# Medusa-AI-ESP.net
KiCad netlist of a schematic drawn in Altium Designer
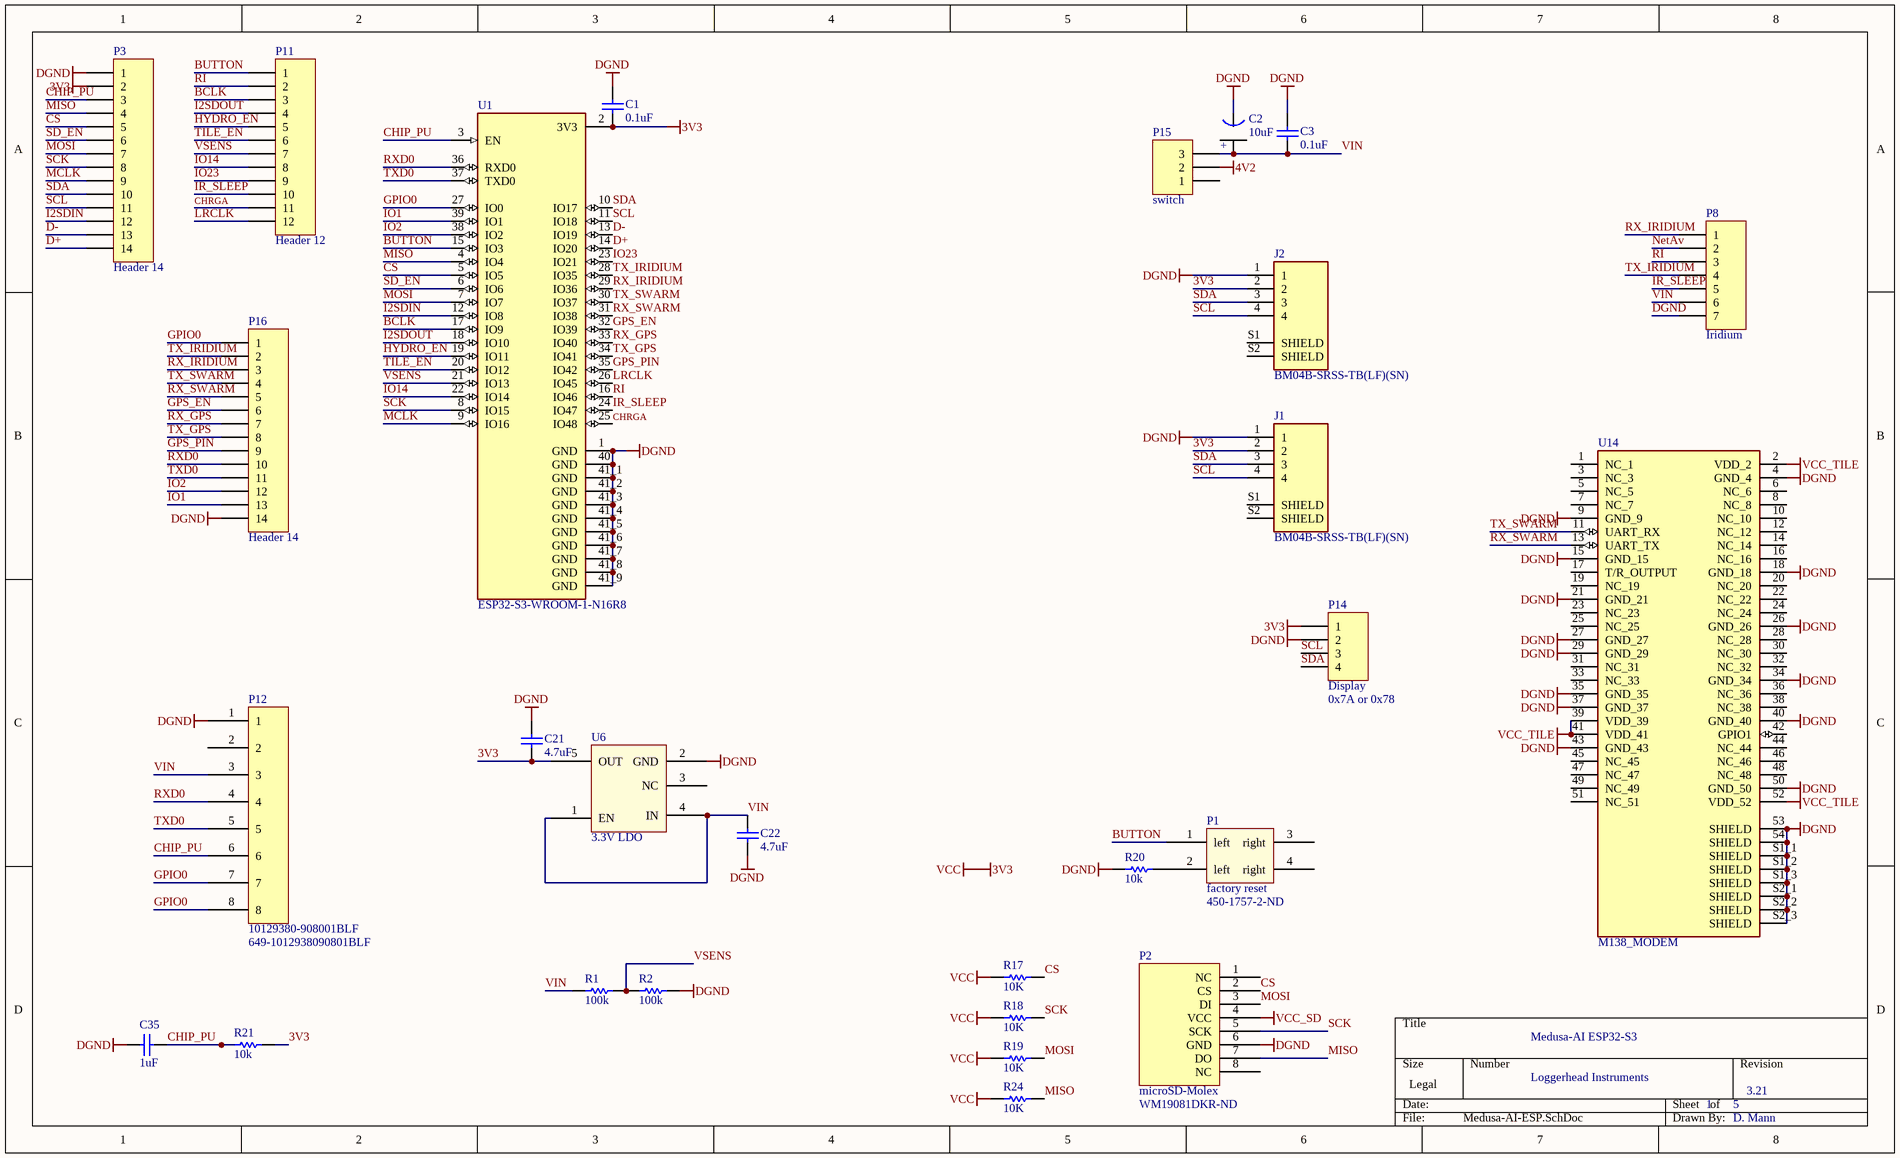
[diagram p0: Medusa-AI-ESP.SchDoc]

(export (version "E")
  (design (tool "Eeschema 10.0.6"))
  (components
    (comp (ref "C1")
      (value "0.1uF")
      (footprint "0402")
      (description "Ceramic Chip Capacitor - Standard")
      (fields (field (name "PUBLISHER") "Altium Limited"))
      (libsource (lib "KEMET Chip Capacitor") (part "C0402"))
    )
    (comp (ref "C2") (value "10uF") (footprint "Tant0805") (libsource (lib "Loggerhead") (part "Tant0805")))
    (comp (ref "C3")
      (value "0.1uF")
      (footprint "0402")
      (description "Ceramic Chip Capacitor - Standard")
      (fields (field (name "PUBLISHER") "Altium Limited"))
      (libsource (lib "KEMET Chip Capacitor") (part "C0402"))
    )
    (comp (ref "C21")
      (value "4.7uF")
      (footprint "0402")
      (description "Ceramic Chip Capacitor - Standard")
      (fields (field (name "PUBLISHER") "Altium Limited"))
      (libsource (lib "KEMET Chip Capacitor") (part "C0402"))
    )
    (comp (ref "C22")
      (value "4.7uF")
      (footprint "0402")
      (description "Ceramic Chip Capacitor - Standard")
      (fields (field (name "PUBLISHER") "Altium Limited"))
      (libsource (lib "KEMET Chip Capacitor") (part "C0402"))
    )
    (comp (ref "C35")
      (value "1uF")
      (footprint "0402")
      (description "Ceramic Chip Capacitor - Standard")
      (fields (field (name "PUBLISHER") "Altium Limited"))
      (libsource (lib "KEMET Chip Capacitor") (part "C0402"))
    )
    (comp (ref "J1")
      (value "BM04B-SRSS-TB(LF)(SN)")
      (footprint "CONN_BM04B-SRSS-TB(LF)(SN)")
      (description "Connector Header Surface Mount 4 position 0.039 _1.00mm_")
      (fields (field (name "MF") "JST Sales") (field (name "MP") "BM04B-SRSS-TB_LF__SN_"))
      (libsource (lib "BM04B-SRSS-TB_LF__SN_") (part "BM04B-SRSS-TB(LF)(SN)"))
    )
    (comp (ref "J2")
      (value "BM04B-SRSS-TB(LF)(SN)")
      (footprint "CONN_BM04B-SRSS-TB(LF)(SN)")
      (description "Connector Header Surface Mount 4 position 0.039 _1.00mm_")
      (fields (field (name "MF") "JST Sales") (field (name "MP") "BM04B-SRSS-TB_LF__SN_"))
      (libsource (lib "BM04B-SRSS-TB_LF__SN_") (part "BM04B-SRSS-TB(LF)(SN)"))
    )
    (comp (ref "P1")
      (value "factory reset")
      (footprint "SOP4")
      (fields (field (name "SUPPLIER PART NUMBER 1") "450-1757-2-ND"))
      (libsource (lib "Loggerhead") (part "pushbutton"))
    )
    (comp (ref "P2")
      (value "microSD-Molex")
      (footprint "microSD_Molex_hinged")
      (fields (field (name "SUPPLIER PART NUMBER 1") "WM19081DKR-ND"))
      (libsource (lib "Loggerhead") (part "microSD_Molex_hinged"))
    )
    (comp (ref "P3")
      (value "Header 14")
      (footprint "HDR1X14")
      (description "Header, 14-Pin")
      (fields (field (name "PUBLISHER") "Altium Limited"))
      (libsource (lib "Miscellaneous Connectors") (part "Header 14"))
    )
    (comp (ref "P8")
      (value "Iridium")
      (footprint "HDR1X7")
      (description "Header, 7-Pin")
      (fields (field (name "PUBLISHER") "Altium Limited"))
      (libsource (lib "Miscellaneous Connectors") (part "Header 7"))
    )
    (comp (ref "P11")
      (value "Header 12")
      (footprint "HDR1X12")
      (description "Header, 12-Pin")
      (fields (field (name "PUBLISHER") "Altium Limited"))
      (libsource (lib "Miscellaneous Connectors") (part "Header 12"))
    )
    (comp (ref "P12")
      (value "10129380-908001BLF")
      (footprint "Header_8_SMT")
      (description "Surface mount header")
      (fields (field (name "SUPPLIER PART NUMBER 1") "649-1012938090801BLF"))
      (libsource (lib "Loggerhead") (part "Header8_SMT"))
    )
    (comp (ref "P14")
      (value "Display")
      (footprint "HDR1X4")
      (description "Header, 4-Pin")
      (fields (field (name "PUBLISHER") "Altium Limited"))
      (libsource (lib "Miscellaneous Connectors") (part "Header 4"))
    )
    (comp (ref "P15")
      (value "switch")
      (footprint "HDR1X3")
      (description "Header, 3-Pin")
      (fields (field (name "PUBLISHER") "Altium Limited"))
      (libsource (lib "Miscellaneous Connectors") (part "Header 3"))
    )
    (comp (ref "P16")
      (value "Header 14")
      (footprint "HDR1X14")
      (description "Header, 14-Pin")
      (fields (field (name "PUBLISHER") "Altium Limited"))
      (libsource (lib "Miscellaneous Connectors") (part "Header 14"))
    )
    (comp (ref "R1")
      (value "100k")
      (footprint "3-0603")
      (fields (field (name "PUBLISHER") "Altium Limited"))
      (libsource (lib "Panasonic Resistor") (part "ERJ3RK"))
    )
    (comp (ref "R2")
      (value "100k")
      (footprint "3-0603")
      (fields (field (name "PUBLISHER") "Altium Limited"))
      (libsource (lib "Panasonic Resistor") (part "ERJ3RK"))
    )
    (comp (ref "R17")
      (value "10K")
      (footprint "3-0603")
      (fields (field (name "PUBLISHER") "Altium Limited"))
      (libsource (lib "Panasonic Resistor") (part "ERJ3EK"))
    )
    (comp (ref "R18")
      (value "10K")
      (footprint "3-0603")
      (fields (field (name "PUBLISHER") "Altium Limited"))
      (libsource (lib "Panasonic Resistor") (part "ERJ3EK"))
    )
    (comp (ref "R19")
      (value "10K")
      (footprint "3-0603")
      (fields (field (name "PUBLISHER") "Altium Limited"))
      (libsource (lib "Panasonic Resistor") (part "ERJ3EK"))
    )
    (comp (ref "R20")
      (value "10k")
      (footprint "2-0402")
      (fields (field (name "PUBLISHER") "Altium Limited"))
      (libsource (lib "Panasonic Resistor") (part "ERJ2RB"))
    )
    (comp (ref "R21")
      (value "10k")
      (footprint "2-0402")
      (fields (field (name "PUBLISHER") "Altium Limited"))
      (libsource (lib "Panasonic Resistor") (part "ERJ2RB"))
    )
    (comp (ref "R24")
      (value "10K")
      (footprint "3-0603")
      (fields (field (name "PUBLISHER") "Altium Limited"))
      (libsource (lib "Panasonic Resistor") (part "ERJ3EK"))
    )
    (comp (ref "U1")
      (value "ESP32-S3-WROOM-1-N16R8")
      (footprint "XCVR_ESP32-S3-WROOM-1-N16R2")
      (description "Bluetooth, WiFi 802.11b/g/n, Bluetooth v5.0 Transceiver Module 2.4GHz PCB Trace Surface Mount")
      (fields (field (name "MP") "ESP32-S3-WROOM-1-N16R2") (field (name "MF") "Espressif Systems"))
      (libsource (lib "ESP32-S3-WROOM-1-N16R2") (part "ESP32-S3-WROOM-1-N16R2"))
    )
    (comp (ref "U6")
      (value "3.3V LDO")
      (footprint "AP7361C-33Y5-13")
      (libsource (lib "Loggerhead") (part "AP7361C-33Y5-13"))
    )
    (comp (ref "U14")
      (value "M138_MODEM")
      (footprint "XCVR_M138_MODEM")
      (description "Swarm M138 Modem")
      (fields (field (name "MF") "Swarm") (field (name "MP") "M138 Modem"))
      (libsource (lib "M138_MODEM") (part "M138_MODEM"))
    )
  )
  (nets
    (net (code "1") (name "/BCLK") (class "Default")
      (node (ref "P11") (pin "3") (pinfunction "3_3") (pintype "passive"))
      (node (ref "U1") (pin "17") (pinfunction "IO9_17") (pintype "bidirectional"))
    )
    (net (code "2") (name "/BUTTON") (class "Default")
      (node (ref "P1") (pin "1") (pinfunction "left_1") (pintype "passive"))
      (node (ref "P11") (pin "1") (pinfunction "1_1") (pintype "passive"))
      (node (ref "U1") (pin "15") (pinfunction "IO3_15") (pintype "bidirectional"))
    )
    (net (code "3") (name "/CHIP_PU") (class "Default")
      (node (ref "C35") (pin "1") (pinfunction "1_1") (pintype "passive"))
      (node (ref "P12") (pin "6") (pinfunction "6_6") (pintype "passive"))
      (node (ref "P3") (pin "3") (pinfunction "3_3") (pintype "passive"))
      (node (ref "R21") (pin "2") (pinfunction "2_2") (pintype "passive"))
      (node (ref "U1") (pin "3") (pinfunction "EN_3") (pintype "input"))
    )
    (net (code "4") (name "/CHRGA") (class "Default")
      (node (ref "P11") (pin "11") (pinfunction "11_11") (pintype "passive"))
      (node (ref "U1") (pin "25") (pinfunction "IO48_25") (pintype "bidirectional"))
    )
    (net (code "5") (name "/CS") (class "Default")
      (node (ref "P2") (pin "2") (pinfunction "CS_2") (pintype "passive"))
      (node (ref "P3") (pin "5") (pinfunction "5_5") (pintype "passive"))
      (node (ref "R17") (pin "2") (pinfunction "2_2") (pintype "passive"))
      (node (ref "U1") (pin "5") (pinfunction "IO5_5") (pintype "bidirectional"))
    )
    (net (code "6") (name "/D+") (class "Default")
      (node (ref "P3") (pin "14") (pinfunction "14_14") (pintype "passive"))
      (node (ref "U1") (pin "14") (pinfunction "IO20_14") (pintype "bidirectional"))
    )
    (net (code "7") (name "/D-") (class "Default")
      (node (ref "P3") (pin "13") (pinfunction "13_13") (pintype "passive"))
      (node (ref "U1") (pin "13") (pinfunction "IO19_13") (pintype "bidirectional"))
    )
    (net (code "8") (name "/GPIO0") (class "Default")
      (node (ref "P12") (pin "7") (pinfunction "7_7") (pintype "passive"))
      (node (ref "P12") (pin "8") (pinfunction "8_8") (pintype "passive"))
      (node (ref "P16") (pin "1") (pinfunction "1_1") (pintype "passive"))
      (node (ref "U1") (pin "27") (pinfunction "IO0_27") (pintype "bidirectional"))
    )
    (net (code "9") (name "/GPS_EN") (class "Default")
      (node (ref "P16") (pin "6") (pinfunction "6_6") (pintype "passive"))
      (node (ref "U1") (pin "32") (pinfunction "IO39_32") (pintype "bidirectional"))
    )
    (net (code "10") (name "/GPS_PIN") (class "Default")
      (node (ref "P16") (pin "9") (pinfunction "9_9") (pintype "passive"))
      (node (ref "U1") (pin "35") (pinfunction "IO42_35") (pintype "bidirectional"))
    )
    (net (code "11") (name "/HYDRO_EN") (class "Default")
      (node (ref "P11") (pin "5") (pinfunction "5_5") (pintype "passive"))
      (node (ref "U1") (pin "19") (pinfunction "IO11_19") (pintype "bidirectional"))
    )
    (net (code "12") (name "/I2SDIN") (class "Default")
      (node (ref "P3") (pin "12") (pinfunction "12_12") (pintype "passive"))
      (node (ref "U1") (pin "12") (pinfunction "IO8_12") (pintype "bidirectional"))
    )
    (net (code "13") (name "/I2SDOUT") (class "Default")
      (node (ref "P11") (pin "4") (pinfunction "4_4") (pintype "passive"))
      (node (ref "U1") (pin "18") (pinfunction "IO10_18") (pintype "bidirectional"))
    )
    (net (code "14") (name "/IO1") (class "Default")
      (node (ref "P16") (pin "13") (pinfunction "13_13") (pintype "passive"))
      (node (ref "U1") (pin "39") (pinfunction "IO1_39") (pintype "bidirectional"))
    )
    (net (code "15") (name "/IO2") (class "Default")
      (node (ref "P16") (pin "12") (pinfunction "12_12") (pintype "passive"))
      (node (ref "U1") (pin "38") (pinfunction "IO2_38") (pintype "bidirectional"))
    )
    (net (code "16") (name "/IO14") (class "Default")
      (node (ref "P11") (pin "8") (pinfunction "8_8") (pintype "passive"))
      (node (ref "U1") (pin "22") (pinfunction "IO14_22") (pintype "bidirectional"))
    )
    (net (code "17") (name "/IO23") (class "Default")
      (node (ref "P11") (pin "9") (pinfunction "9_9") (pintype "passive"))
      (node (ref "U1") (pin "23") (pinfunction "IO21_23") (pintype "bidirectional"))
    )
    (net (code "18") (name "/IR_SLEEP") (class "Default")
      (node (ref "P11") (pin "10") (pinfunction "10_10") (pintype "passive"))
      (node (ref "P8") (pin "5") (pinfunction "5_5") (pintype "passive"))
      (node (ref "U1") (pin "24") (pinfunction "IO47_24") (pintype "bidirectional"))
    )
    (net (code "19") (name "/LRCLK") (class "Default")
      (node (ref "P11") (pin "12") (pinfunction "12_12") (pintype "passive"))
      (node (ref "U1") (pin "26") (pinfunction "IO45_26") (pintype "bidirectional"))
    )
    (net (code "20") (name "/MCLK") (class "Default")
      (node (ref "P3") (pin "9") (pinfunction "9_9") (pintype "passive"))
      (node (ref "U1") (pin "9") (pinfunction "IO16_9") (pintype "bidirectional"))
    )
    (net (code "21") (name "/MISO") (class "Default")
      (node (ref "P2") (pin "7") (pinfunction "DO_7") (pintype "passive"))
      (node (ref "P3") (pin "4") (pinfunction "4_4") (pintype "passive"))
      (node (ref "R24") (pin "2") (pinfunction "2_2") (pintype "passive"))
      (node (ref "U1") (pin "4") (pinfunction "IO4_4") (pintype "bidirectional"))
    )
    (net (code "22") (name "/MOSI") (class "Default")
      (node (ref "P2") (pin "3") (pinfunction "DI_3") (pintype "passive"))
      (node (ref "P3") (pin "7") (pinfunction "7_7") (pintype "passive"))
      (node (ref "R19") (pin "2") (pinfunction "2_2") (pintype "passive"))
      (node (ref "U1") (pin "7") (pinfunction "IO7_7") (pintype "bidirectional"))
    )
    (net (code "23") (name "/NetAv") (class "Default")
      (node (ref "P8") (pin "2") (pinfunction "2_2") (pintype "passive"))
    )
    (net (code "24") (name "/RI") (class "Default")
      (node (ref "P11") (pin "2") (pinfunction "2_2") (pintype "passive"))
      (node (ref "P8") (pin "3") (pinfunction "3_3") (pintype "passive"))
      (node (ref "U1") (pin "16") (pinfunction "IO46_16") (pintype "bidirectional"))
    )
    (net (code "25") (name "/RXD0") (class "Default")
      (node (ref "P12") (pin "4") (pinfunction "4_4") (pintype "passive"))
      (node (ref "P16") (pin "10") (pinfunction "10_10") (pintype "passive"))
      (node (ref "U1") (pin "36") (pinfunction "RXD0_36") (pintype "bidirectional"))
    )
    (net (code "26") (name "/RX_GPS") (class "Default")
      (node (ref "P16") (pin "7") (pinfunction "7_7") (pintype "passive"))
      (node (ref "U1") (pin "33") (pinfunction "IO40_33") (pintype "bidirectional"))
    )
    (net (code "27") (name "/RX_IRIDIUM") (class "Default")
      (node (ref "P16") (pin "3") (pinfunction "3_3") (pintype "passive"))
      (node (ref "P8") (pin "1") (pinfunction "1_1") (pintype "passive"))
      (node (ref "U1") (pin "29") (pinfunction "IO36_29") (pintype "bidirectional"))
    )
    (net (code "28") (name "/RX_SWARM") (class "Default")
      (node (ref "P16") (pin "5") (pinfunction "5_5") (pintype "passive"))
      (node (ref "U1") (pin "31") (pinfunction "IO38_31") (pintype "bidirectional"))
      (node (ref "U14") (pin "13") (pinfunction "UART_TX_13") (pintype "bidirectional"))
    )
    (net (code "29") (name "/SCK") (class "Default")
      (node (ref "P2") (pin "5") (pinfunction "SCK_5") (pintype "passive"))
      (node (ref "P3") (pin "8") (pinfunction "8_8") (pintype "passive"))
      (node (ref "R18") (pin "2") (pinfunction "2_2") (pintype "passive"))
      (node (ref "U1") (pin "8") (pinfunction "IO15_8") (pintype "bidirectional"))
    )
    (net (code "30") (name "/SCL") (class "Default")
      (node (ref "J1") (pin "4") (pinfunction "4_4") (pintype "passive"))
      (node (ref "J2") (pin "4") (pinfunction "4_4") (pintype "passive"))
      (node (ref "P14") (pin "3") (pinfunction "3_3") (pintype "passive"))
      (node (ref "P3") (pin "11") (pinfunction "11_11") (pintype "passive"))
      (node (ref "U1") (pin "11") (pinfunction "IO18_11") (pintype "bidirectional"))
    )
    (net (code "31") (name "/SDA") (class "Default")
      (node (ref "J1") (pin "3") (pinfunction "3_3") (pintype "passive"))
      (node (ref "J2") (pin "3") (pinfunction "3_3") (pintype "passive"))
      (node (ref "P14") (pin "4") (pinfunction "4_4") (pintype "passive"))
      (node (ref "P3") (pin "10") (pinfunction "10_10") (pintype "passive"))
      (node (ref "U1") (pin "10") (pinfunction "IO17_10") (pintype "bidirectional"))
    )
    (net (code "32") (name "/SD_EN") (class "Default")
      (node (ref "P3") (pin "6") (pinfunction "6_6") (pintype "passive"))
      (node (ref "U1") (pin "6") (pinfunction "IO6_6") (pintype "bidirectional"))
    )
    (net (code "33") (name "/TILE_EN") (class "Default")
      (node (ref "P11") (pin "6") (pinfunction "6_6") (pintype "passive"))
      (node (ref "U1") (pin "20") (pinfunction "IO12_20") (pintype "bidirectional"))
    )
    (net (code "34") (name "/TXD0") (class "Default")
      (node (ref "P12") (pin "5") (pinfunction "5_5") (pintype "passive"))
      (node (ref "P16") (pin "11") (pinfunction "11_11") (pintype "passive"))
      (node (ref "U1") (pin "37") (pinfunction "TXD0_37") (pintype "bidirectional"))
    )
    (net (code "35") (name "/TX_GPS") (class "Default")
      (node (ref "P16") (pin "8") (pinfunction "8_8") (pintype "passive"))
      (node (ref "U1") (pin "34") (pinfunction "IO41_34") (pintype "bidirectional"))
    )
    (net (code "36") (name "/TX_IRIDIUM") (class "Default")
      (node (ref "P16") (pin "2") (pinfunction "2_2") (pintype "passive"))
      (node (ref "P8") (pin "4") (pinfunction "4_4") (pintype "passive"))
      (node (ref "U1") (pin "28") (pinfunction "IO35_28") (pintype "bidirectional"))
    )
    (net (code "37") (name "/TX_SWARM") (class "Default")
      (node (ref "P16") (pin "4") (pinfunction "4_4") (pintype "passive"))
      (node (ref "U1") (pin "30") (pinfunction "IO37_30") (pintype "bidirectional"))
      (node (ref "U14") (pin "11") (pinfunction "UART_RX_11") (pintype "bidirectional"))
    )
    (net (code "38") (name "/VIN") (class "Default")
      (node (ref "C2") (pin "2") (pinfunction "+_2") (pintype "passive"))
      (node (ref "C22") (pin "1") (pinfunction "1_1") (pintype "passive"))
      (node (ref "C3") (pin "1") (pinfunction "1_1") (pintype "passive"))
      (node (ref "P12") (pin "3") (pinfunction "3_3") (pintype "passive"))
      (node (ref "P15") (pin "3") (pinfunction "3_3") (pintype "passive"))
      (node (ref "P8") (pin "6") (pinfunction "6_6") (pintype "passive"))
      (node (ref "R1") (pin "2") (pinfunction "2_2") (pintype "passive"))
      (node (ref "U6") (pin "1") (pinfunction "EN_1") (pintype "passive"))
      (node (ref "U6") (pin "4") (pinfunction "IN_4") (pintype "passive"))
    )
    (net (code "39") (name "/VSENS") (class "Default")
      (node (ref "P11") (pin "7") (pinfunction "7_7") (pintype "passive"))
      (node (ref "R1") (pin "1") (pinfunction "1_1") (pintype "passive"))
      (node (ref "R2") (pin "2") (pinfunction "2_2") (pintype "passive"))
      (node (ref "U1") (pin "21") (pinfunction "IO13_21") (pintype "bidirectional"))
    )
    (net (code "40") (name "3V3") (class "Default")
      (node (ref "C1") (pin "1") (pinfunction "1_1") (pintype "passive"))
      (node (ref "C21") (pin "2") (pinfunction "2_2") (pintype "passive"))
      (node (ref "J1") (pin "2") (pinfunction "2_2") (pintype "passive"))
      (node (ref "J2") (pin "2") (pinfunction "2_2") (pintype "passive"))
      (node (ref "P14") (pin "1") (pinfunction "1_1") (pintype "passive"))
      (node (ref "P3") (pin "2") (pinfunction "2_2") (pintype "passive"))
      (node (ref "R17") (pin "1") (pinfunction "1_1") (pintype "passive"))
      (node (ref "R18") (pin "1") (pinfunction "1_1") (pintype "passive"))
      (node (ref "R19") (pin "1") (pinfunction "1_1") (pintype "passive"))
      (node (ref "R21") (pin "1") (pinfunction "1_1") (pintype "passive"))
      (node (ref "R24") (pin "1") (pinfunction "1_1") (pintype "passive"))
      (node (ref "U1") (pin "2") (pinfunction "3V3_2") (pintype "power_in"))
      (node (ref "U6") (pin "5") (pinfunction "OUT_5") (pintype "passive"))
    )
    (net (code "41") (name "4V2") (class "Default")
      (node (ref "P15") (pin "2") (pinfunction "2_2") (pintype "passive"))
    )
    (net (code "42") (name "DGND") (class "Default")
      (node (ref "C1") (pin "2") (pinfunction "2_2") (pintype "passive"))
      (node (ref "C2") (pin "1") (pinfunction "GND_1") (pintype "passive"))
      (node (ref "C21") (pin "1") (pinfunction "1_1") (pintype "passive"))
      (node (ref "C22") (pin "2") (pinfunction "2_2") (pintype "passive"))
      (node (ref "C3") (pin "2") (pinfunction "2_2") (pintype "passive"))
      (node (ref "C35") (pin "2") (pinfunction "2_2") (pintype "passive"))
      (node (ref "J1") (pin "1") (pinfunction "1_1") (pintype "passive"))
      (node (ref "J2") (pin "1") (pinfunction "1_1") (pintype "passive"))
      (node (ref "P12") (pin "1") (pinfunction "1_1") (pintype "passive"))
      (node (ref "P14") (pin "2") (pinfunction "2_2") (pintype "passive"))
      (node (ref "P16") (pin "14") (pinfunction "14_14") (pintype "passive"))
      (node (ref "P2") (pin "6") (pinfunction "GND_6") (pintype "passive"))
      (node (ref "P3") (pin "1") (pinfunction "1_1") (pintype "passive"))
      (node (ref "P8") (pin "7") (pinfunction "7_7") (pintype "passive"))
      (node (ref "R2") (pin "1") (pinfunction "1_1") (pintype "passive"))
      (node (ref "R20") (pin "2") (pinfunction "2_2") (pintype "passive"))
      (node (ref "U1") (pin "1") (pinfunction "GND_1") (pintype "power_in"))
      (node (ref "U1") (pin "40") (pinfunction "GND_40") (pintype "power_in"))
      (node (ref "U1") (pin "41_1") (pinfunction "GND_41_1") (pintype "power_in"))
      (node (ref "U1") (pin "41_2") (pinfunction "GND_41_2") (pintype "power_in"))
      (node (ref "U1") (pin "41_3") (pinfunction "GND_41_3") (pintype "power_in"))
      (node (ref "U1") (pin "41_4") (pinfunction "GND_41_4") (pintype "power_in"))
      (node (ref "U1") (pin "41_5") (pinfunction "GND_41_5") (pintype "power_in"))
      (node (ref "U1") (pin "41_6") (pinfunction "GND_41_6") (pintype "power_in"))
      (node (ref "U1") (pin "41_7") (pinfunction "GND_41_7") (pintype "power_in"))
      (node (ref "U1") (pin "41_8") (pinfunction "GND_41_8") (pintype "power_in"))
      (node (ref "U1") (pin "41_9") (pinfunction "GND_41_9") (pintype "power_in"))
      (node (ref "U14") (pin "15") (pinfunction "GND_15_15") (pintype "power_in"))
      (node (ref "U14") (pin "18") (pinfunction "GND_18_18") (pintype "power_in"))
      (node (ref "U14") (pin "21") (pinfunction "GND_21_21") (pintype "power_in"))
      (node (ref "U14") (pin "26") (pinfunction "GND_26_26") (pintype "power_in"))
      (node (ref "U14") (pin "27") (pinfunction "GND_27_27") (pintype "power_in"))
      (node (ref "U14") (pin "29") (pinfunction "GND_29_29") (pintype "power_in"))
      (node (ref "U14") (pin "34") (pinfunction "GND_34_34") (pintype "power_in"))
      (node (ref "U14") (pin "35") (pinfunction "GND_35_35") (pintype "power_in"))
      (node (ref "U14") (pin "37") (pinfunction "GND_37_37") (pintype "power_in"))
      (node (ref "U14") (pin "4") (pinfunction "GND_4_4") (pintype "power_in"))
      (node (ref "U14") (pin "40") (pinfunction "GND_40_40") (pintype "power_in"))
      (node (ref "U14") (pin "43") (pinfunction "GND_43_43") (pintype "power_in"))
      (node (ref "U14") (pin "50") (pinfunction "GND_50_50") (pintype "power_in"))
      (node (ref "U14") (pin "53") (pinfunction "SHIELD_53") (pintype "passive"))
      (node (ref "U14") (pin "54") (pinfunction "SHIELD_54") (pintype "passive"))
      (node (ref "U14") (pin "9") (pinfunction "GND_9_9") (pintype "power_in"))
      (node (ref "U14") (pin "S1_1") (pinfunction "SHIELD_S1_1") (pintype "passive"))
      (node (ref "U14") (pin "S1_2") (pinfunction "SHIELD_S1_2") (pintype "passive"))
      (node (ref "U14") (pin "S1_3") (pinfunction "SHIELD_S1_3") (pintype "passive"))
      (node (ref "U14") (pin "S2_1") (pinfunction "SHIELD_S2_1") (pintype "passive"))
      (node (ref "U14") (pin "S2_2") (pinfunction "SHIELD_S2_2") (pintype "passive"))
      (node (ref "U14") (pin "S2_3") (pinfunction "SHIELD_S2_3") (pintype "passive"))
      (node (ref "U6") (pin "2") (pinfunction "GND_2") (pintype "passive"))
    )
    (net (code "43") (name "Net-(P1-left-Pad2)") (class "Default")
      (node (ref "P1") (pin "2") (pinfunction "left_2") (pintype "passive"))
      (node (ref "R20") (pin "1") (pinfunction "1_1") (pintype "passive"))
    )
    (net (code "44") (name "VCC_SD") (class "Default")
      (node (ref "P2") (pin "4") (pinfunction "VCC_4") (pintype "passive"))
    )
    (net (code "45") (name "VCC_TILE") (class "Default")
      (node (ref "U14") (pin "2") (pinfunction "VDD_2_2") (pintype "power_in"))
      (node (ref "U14") (pin "39") (pinfunction "VDD_39_39") (pintype "power_in"))
      (node (ref "U14") (pin "41") (pinfunction "VDD_41_41") (pintype "power_in"))
      (node (ref "U14") (pin "52") (pinfunction "VDD_52_52") (pintype "power_in"))
    )
    (net (code "46") (name "unconnected-(J1-SHIELD-PadS1)") (class "Default")
      (node (ref "J1") (pin "S1") (pinfunction "SHIELD_S1") (pintype "passive"))
    )
    (net (code "47") (name "unconnected-(J1-SHIELD-PadS2)") (class "Default")
      (node (ref "J1") (pin "S2") (pinfunction "SHIELD_S2") (pintype "passive"))
    )
    (net (code "48") (name "unconnected-(J2-SHIELD-PadS1)") (class "Default")
      (node (ref "J2") (pin "S1") (pinfunction "SHIELD_S1") (pintype "passive"))
    )
    (net (code "49") (name "unconnected-(J2-SHIELD-PadS2)") (class "Default")
      (node (ref "J2") (pin "S2") (pinfunction "SHIELD_S2") (pintype "passive"))
    )
    (net (code "50") (name "unconnected-(P1-right-Pad3)") (class "Default")
      (node (ref "P1") (pin "3") (pinfunction "right_3") (pintype "passive"))
    )
    (net (code "51") (name "unconnected-(P1-right-Pad4)") (class "Default")
      (node (ref "P1") (pin "4") (pinfunction "right_4") (pintype "passive"))
    )
    (net (code "52") (name "unconnected-(P2-NC-Pad1)") (class "Default")
      (node (ref "P2") (pin "1") (pinfunction "NC_1") (pintype "passive"))
    )
    (net (code "53") (name "unconnected-(P2-NC-Pad8)") (class "Default")
      (node (ref "P2") (pin "8") (pinfunction "NC_8") (pintype "passive"))
    )
    (net (code "54") (name "unconnected-(P12-Pad2)") (class "Default")
      (node (ref "P12") (pin "2") (pinfunction "2_2") (pintype "passive"))
    )
    (net (code "55") (name "unconnected-(P15-Pad1)") (class "Default")
      (node (ref "P15") (pin "1") (pinfunction "1_1") (pintype "passive"))
    )
    (net (code "56") (name "unconnected-(U6-NC-Pad3)") (class "Default")
      (node (ref "U6") (pin "3") (pinfunction "NC_3") (pintype "passive"))
    )
    (net (code "57") (name "unconnected-(U14-GPIO1-Pad42)") (class "Default")
      (node (ref "U14") (pin "42") (pinfunction "GPIO1_42") (pintype "bidirectional"))
    )
    (net (code "58") (name "unconnected-(U14-NC_1-Pad1)") (class "Default")
      (node (ref "U14") (pin "1") (pinfunction "NC_1_1") (pintype "passive"))
    )
    (net (code "59") (name "unconnected-(U14-NC_3-Pad3)") (class "Default")
      (node (ref "U14") (pin "3") (pinfunction "NC_3_3") (pintype "passive"))
    )
    (net (code "60") (name "unconnected-(U14-NC_5-Pad5)") (class "Default")
      (node (ref "U14") (pin "5") (pinfunction "NC_5_5") (pintype "passive"))
    )
    (net (code "61") (name "unconnected-(U14-NC_6-Pad6)") (class "Default")
      (node (ref "U14") (pin "6") (pinfunction "NC_6_6") (pintype "passive"))
    )
    (net (code "62") (name "unconnected-(U14-NC_7-Pad7)") (class "Default")
      (node (ref "U14") (pin "7") (pinfunction "NC_7_7") (pintype "passive"))
    )
    (net (code "63") (name "unconnected-(U14-NC_8-Pad8)") (class "Default")
      (node (ref "U14") (pin "8") (pinfunction "NC_8_8") (pintype "passive"))
    )
    (net (code "64") (name "unconnected-(U14-NC_10-Pad10)") (class "Default")
      (node (ref "U14") (pin "10") (pinfunction "NC_10_10") (pintype "passive"))
    )
    (net (code "65") (name "unconnected-(U14-NC_12-Pad12)") (class "Default")
      (node (ref "U14") (pin "12") (pinfunction "NC_12_12") (pintype "passive"))
    )
    (net (code "66") (name "unconnected-(U14-NC_14-Pad14)") (class "Default")
      (node (ref "U14") (pin "14") (pinfunction "NC_14_14") (pintype "passive"))
    )
    (net (code "67") (name "unconnected-(U14-NC_16-Pad16)") (class "Default")
      (node (ref "U14") (pin "16") (pinfunction "NC_16_16") (pintype "passive"))
    )
    (net (code "68") (name "unconnected-(U14-NC_19-Pad19)") (class "Default")
      (node (ref "U14") (pin "19") (pinfunction "NC_19_19") (pintype "passive"))
    )
    (net (code "69") (name "unconnected-(U14-NC_20-Pad20)") (class "Default")
      (node (ref "U14") (pin "20") (pinfunction "NC_20_20") (pintype "passive"))
    )
    (net (code "70") (name "unconnected-(U14-NC_22-Pad22)") (class "Default")
      (node (ref "U14") (pin "22") (pinfunction "NC_22_22") (pintype "passive"))
    )
    (net (code "71") (name "unconnected-(U14-NC_23-Pad23)") (class "Default")
      (node (ref "U14") (pin "23") (pinfunction "NC_23_23") (pintype "passive"))
    )
    (net (code "72") (name "unconnected-(U14-NC_24-Pad24)") (class "Default")
      (node (ref "U14") (pin "24") (pinfunction "NC_24_24") (pintype "passive"))
    )
    (net (code "73") (name "unconnected-(U14-NC_25-Pad25)") (class "Default")
      (node (ref "U14") (pin "25") (pinfunction "NC_25_25") (pintype "passive"))
    )
    (net (code "74") (name "unconnected-(U14-NC_28-Pad28)") (class "Default")
      (node (ref "U14") (pin "28") (pinfunction "NC_28_28") (pintype "passive"))
    )
    (net (code "75") (name "unconnected-(U14-NC_30-Pad30)") (class "Default")
      (node (ref "U14") (pin "30") (pinfunction "NC_30_30") (pintype "passive"))
    )
    (net (code "76") (name "unconnected-(U14-NC_31-Pad31)") (class "Default")
      (node (ref "U14") (pin "31") (pinfunction "NC_31_31") (pintype "passive"))
    )
    (net (code "77") (name "unconnected-(U14-NC_32-Pad32)") (class "Default")
      (node (ref "U14") (pin "32") (pinfunction "NC_32_32") (pintype "passive"))
    )
    (net (code "78") (name "unconnected-(U14-NC_33-Pad33)") (class "Default")
      (node (ref "U14") (pin "33") (pinfunction "NC_33_33") (pintype "passive"))
    )
    (net (code "79") (name "unconnected-(U14-NC_36-Pad36)") (class "Default")
      (node (ref "U14") (pin "36") (pinfunction "NC_36_36") (pintype "passive"))
    )
    (net (code "80") (name "unconnected-(U14-NC_38-Pad38)") (class "Default")
      (node (ref "U14") (pin "38") (pinfunction "NC_38_38") (pintype "passive"))
    )
    (net (code "81") (name "unconnected-(U14-NC_44-Pad44)") (class "Default")
      (node (ref "U14") (pin "44") (pinfunction "NC_44_44") (pintype "passive"))
    )
    (net (code "82") (name "unconnected-(U14-NC_45-Pad45)") (class "Default")
      (node (ref "U14") (pin "45") (pinfunction "NC_45_45") (pintype "passive"))
    )
    (net (code "83") (name "unconnected-(U14-NC_46-Pad46)") (class "Default")
      (node (ref "U14") (pin "46") (pinfunction "NC_46_46") (pintype "passive"))
    )
    (net (code "84") (name "unconnected-(U14-NC_47-Pad47)") (class "Default")
      (node (ref "U14") (pin "47") (pinfunction "NC_47_47") (pintype "passive"))
    )
    (net (code "85") (name "unconnected-(U14-NC_48-Pad48)") (class "Default")
      (node (ref "U14") (pin "48") (pinfunction "NC_48_48") (pintype "passive"))
    )
    (net (code "86") (name "unconnected-(U14-NC_49-Pad49)") (class "Default")
      (node (ref "U14") (pin "49") (pinfunction "NC_49_49") (pintype "passive"))
    )
    (net (code "87") (name "unconnected-(U14-NC_51-Pad51)") (class "Default")
      (node (ref "U14") (pin "51") (pinfunction "NC_51_51") (pintype "passive"))
    )
    (net (code "88") (name "unconnected-(U14-T{slash}R_OUTPUT-Pad17)") (class "Default")
      (node (ref "U14") (pin "17") (pinfunction "T/R_OUTPUT_17") (pintype "passive"))
    )
  )
)
